# ShiftRegister.net
KiCad netlist of a schematic drawn in Altium Designer
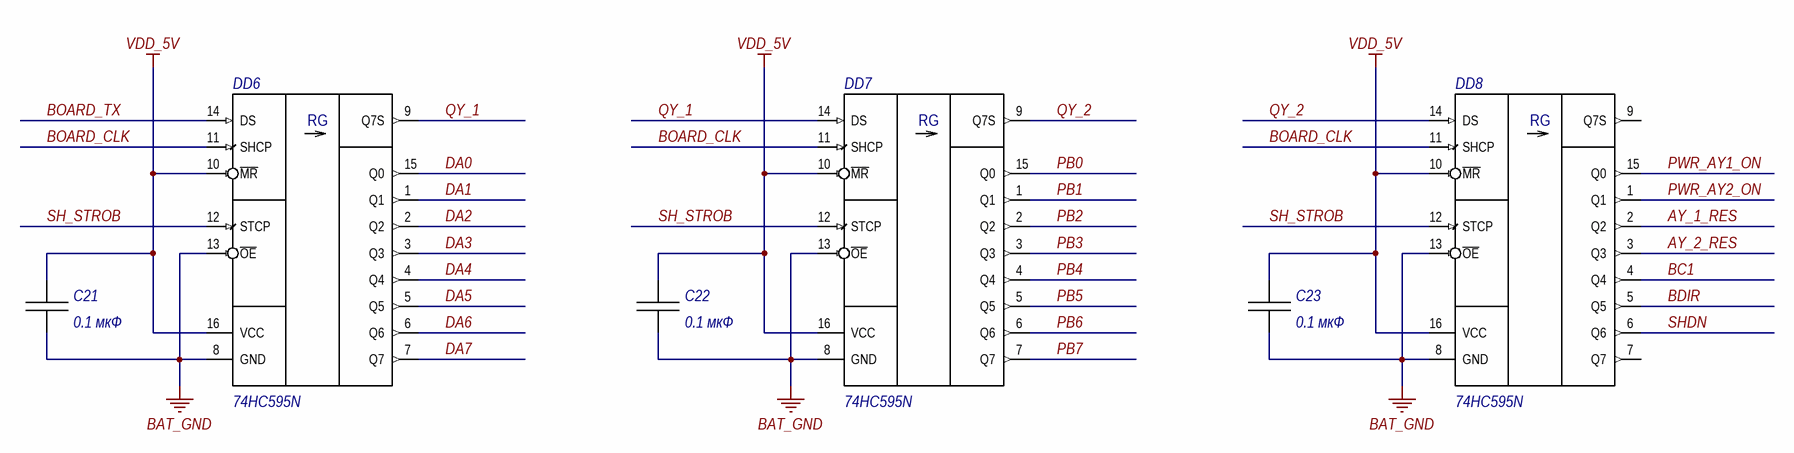
[diagram p0: ShiftRegister.SchDoc]

(export (version "E")
  (design (tool "Eeschema 10.0.6"))
  (components
    (comp (ref "C21")
      (value "0.1 мкФ")
      (footprint "C 1206")
      (description "SMD Capacitor 1206")
      (fields
        (field (name "TOLERANCE") "/Укажите допуск в процентах/")
        (field (name "MANUFACTURER") "/Укажите компанию-производителя/")
      )
      (libsource (lib "my_lib") (part "CAP 1206"))
    )
    (comp (ref "C22")
      (value "0.1 мкФ")
      (footprint "C 1206")
      (description "SMD Capacitor 1206")
      (fields
        (field (name "TOLERANCE") "/Укажите допуск в процентах/")
        (field (name "MANUFACTURER") "/Укажите компанию-производителя/")
      )
      (libsource (lib "my_lib") (part "CAP 1206"))
    )
    (comp (ref "C23")
      (value "0.1 мкФ")
      (footprint "C 1206")
      (description "SMD Capacitor 1206")
      (fields
        (field (name "TOLERANCE") "/Укажите допуск в процентах/")
        (field (name "MANUFACTURER") "/Укажите компанию-производителя/")
      )
      (libsource (lib "my_lib") (part "CAP 1206"))
    )
    (comp (ref "DD6") (value "74HC595N") (footprint "SO16") (libsource (lib "my_lib") (part "74HC595N")))
    (comp (ref "DD7") (value "74HC595N") (footprint "SO16") (libsource (lib "my_lib") (part "74HC595N")))
    (comp (ref "DD8") (value "74HC595N") (footprint "SO16") (libsource (lib "my_lib") (part "74HC595N")))
  )
  (nets
    (net (code "1") (name "/AY_1_RES") (class "Default")
      (node (ref "DD8") (pin "2") (pinfunction "Q2_2") (pintype "output"))
    )
    (net (code "2") (name "/AY_2_RES") (class "Default")
      (node (ref "DD8") (pin "3") (pinfunction "Q3_3") (pintype "output"))
    )
    (net (code "3") (name "/BC1") (class "Default")
      (node (ref "DD8") (pin "4") (pinfunction "Q4_4") (pintype "output"))
    )
    (net (code "4") (name "/BDIR") (class "Default")
      (node (ref "DD8") (pin "5") (pinfunction "Q5_5") (pintype "output"))
    )
    (net (code "5") (name "/BOARD_CLK") (class "Default")
      (node (ref "DD6") (pin "11") (pinfunction "SHCP_11") (pintype "input"))
      (node (ref "DD7") (pin "11") (pinfunction "SHCP_11") (pintype "input"))
      (node (ref "DD8") (pin "11") (pinfunction "SHCP_11") (pintype "input"))
    )
    (net (code "6") (name "/BOARD_TX") (class "Default")
      (node (ref "DD6") (pin "14") (pinfunction "DS_14") (pintype "input"))
    )
    (net (code "7") (name "/DA0") (class "Default")
      (node (ref "DD6") (pin "15") (pinfunction "Q0_15") (pintype "output"))
    )
    (net (code "8") (name "/DA1") (class "Default")
      (node (ref "DD6") (pin "1") (pinfunction "Q1_1") (pintype "output"))
    )
    (net (code "9") (name "/DA2") (class "Default")
      (node (ref "DD6") (pin "2") (pinfunction "Q2_2") (pintype "output"))
    )
    (net (code "10") (name "/DA3") (class "Default")
      (node (ref "DD6") (pin "3") (pinfunction "Q3_3") (pintype "output"))
    )
    (net (code "11") (name "/DA4") (class "Default")
      (node (ref "DD6") (pin "4") (pinfunction "Q4_4") (pintype "output"))
    )
    (net (code "12") (name "/DA5") (class "Default")
      (node (ref "DD6") (pin "5") (pinfunction "Q5_5") (pintype "output"))
    )
    (net (code "13") (name "/DA6") (class "Default")
      (node (ref "DD6") (pin "6") (pinfunction "Q6_6") (pintype "output"))
    )
    (net (code "14") (name "/DA7") (class "Default")
      (node (ref "DD6") (pin "7") (pinfunction "Q7_7") (pintype "output"))
    )
    (net (code "15") (name "/PB0") (class "Default")
      (node (ref "DD7") (pin "15") (pinfunction "Q0_15") (pintype "output"))
    )
    (net (code "16") (name "/PB1") (class "Default")
      (node (ref "DD7") (pin "1") (pinfunction "Q1_1") (pintype "output"))
    )
    (net (code "17") (name "/PB2") (class "Default")
      (node (ref "DD7") (pin "2") (pinfunction "Q2_2") (pintype "output"))
    )
    (net (code "18") (name "/PB3") (class "Default")
      (node (ref "DD7") (pin "3") (pinfunction "Q3_3") (pintype "output"))
    )
    (net (code "19") (name "/PB4") (class "Default")
      (node (ref "DD7") (pin "4") (pinfunction "Q4_4") (pintype "output"))
    )
    (net (code "20") (name "/PB5") (class "Default")
      (node (ref "DD7") (pin "5") (pinfunction "Q5_5") (pintype "output"))
    )
    (net (code "21") (name "/PB6") (class "Default")
      (node (ref "DD7") (pin "6") (pinfunction "Q6_6") (pintype "output"))
    )
    (net (code "22") (name "/PB7") (class "Default")
      (node (ref "DD7") (pin "7") (pinfunction "Q7_7") (pintype "output"))
    )
    (net (code "23") (name "/PWR_AY1_ON") (class "Default")
      (node (ref "DD8") (pin "15") (pinfunction "Q0_15") (pintype "output"))
    )
    (net (code "24") (name "/PWR_AY2_ON") (class "Default")
      (node (ref "DD8") (pin "1") (pinfunction "Q1_1") (pintype "output"))
    )
    (net (code "25") (name "/QY_1") (class "Default")
      (node (ref "DD6") (pin "9") (pinfunction "Q7S_9") (pintype "output"))
      (node (ref "DD7") (pin "14") (pinfunction "DS_14") (pintype "input"))
    )
    (net (code "26") (name "/QY_2") (class "Default")
      (node (ref "DD7") (pin "9") (pinfunction "Q7S_9") (pintype "output"))
      (node (ref "DD8") (pin "14") (pinfunction "DS_14") (pintype "input"))
    )
    (net (code "27") (name "/SHDN") (class "Default")
      (node (ref "DD8") (pin "6") (pinfunction "Q6_6") (pintype "output"))
    )
    (net (code "28") (name "/SH_STROB") (class "Default")
      (node (ref "DD6") (pin "12") (pinfunction "STCP_12") (pintype "input"))
      (node (ref "DD7") (pin "12") (pinfunction "STCP_12") (pintype "input"))
      (node (ref "DD8") (pin "12") (pinfunction "STCP_12") (pintype "input"))
    )
    (net (code "29") (name "BAT_GND") (class "Default")
      (node (ref "C21") (pin "2") (pinfunction "2_2") (pintype "passive"))
      (node (ref "C22") (pin "2") (pinfunction "2_2") (pintype "passive"))
      (node (ref "C23") (pin "2") (pinfunction "2_2") (pintype "passive"))
      (node (ref "DD6") (pin "13") (pinfunction "~{OE}_13") (pintype "input"))
      (node (ref "DD6") (pin "8") (pinfunction "GND_8") (pintype "power_in"))
      (node (ref "DD7") (pin "13") (pinfunction "~{OE}_13") (pintype "input"))
      (node (ref "DD7") (pin "8") (pinfunction "GND_8") (pintype "power_in"))
      (node (ref "DD8") (pin "13") (pinfunction "~{OE}_13") (pintype "input"))
      (node (ref "DD8") (pin "8") (pinfunction "GND_8") (pintype "power_in"))
    )
    (net (code "30") (name "VDD_5V") (class "Default")
      (node (ref "C21") (pin "1") (pinfunction "1_1") (pintype "passive"))
      (node (ref "C22") (pin "1") (pinfunction "1_1") (pintype "passive"))
      (node (ref "C23") (pin "1") (pinfunction "1_1") (pintype "passive"))
      (node (ref "DD6") (pin "10") (pinfunction "~{MR}_10") (pintype "input"))
      (node (ref "DD6") (pin "16") (pinfunction "VCC_16") (pintype "power_in"))
      (node (ref "DD7") (pin "10") (pinfunction "~{MR}_10") (pintype "input"))
      (node (ref "DD7") (pin "16") (pinfunction "VCC_16") (pintype "power_in"))
      (node (ref "DD8") (pin "10") (pinfunction "~{MR}_10") (pintype "input"))
      (node (ref "DD8") (pin "16") (pinfunction "VCC_16") (pintype "power_in"))
    )
    (net (code "31") (name "unconnected-(DD8-Q7-Pad7)") (class "Default")
      (node (ref "DD8") (pin "7") (pinfunction "Q7_7") (pintype "output"))
    )
    (net (code "32") (name "unconnected-(DD8-Q7S-Pad9)") (class "Default")
      (node (ref "DD8") (pin "9") (pinfunction "Q7S_9") (pintype "output"))
    )
  )
)
